# open-lux-B.net
KiCad netlist of a schematic drawn in EAGLE
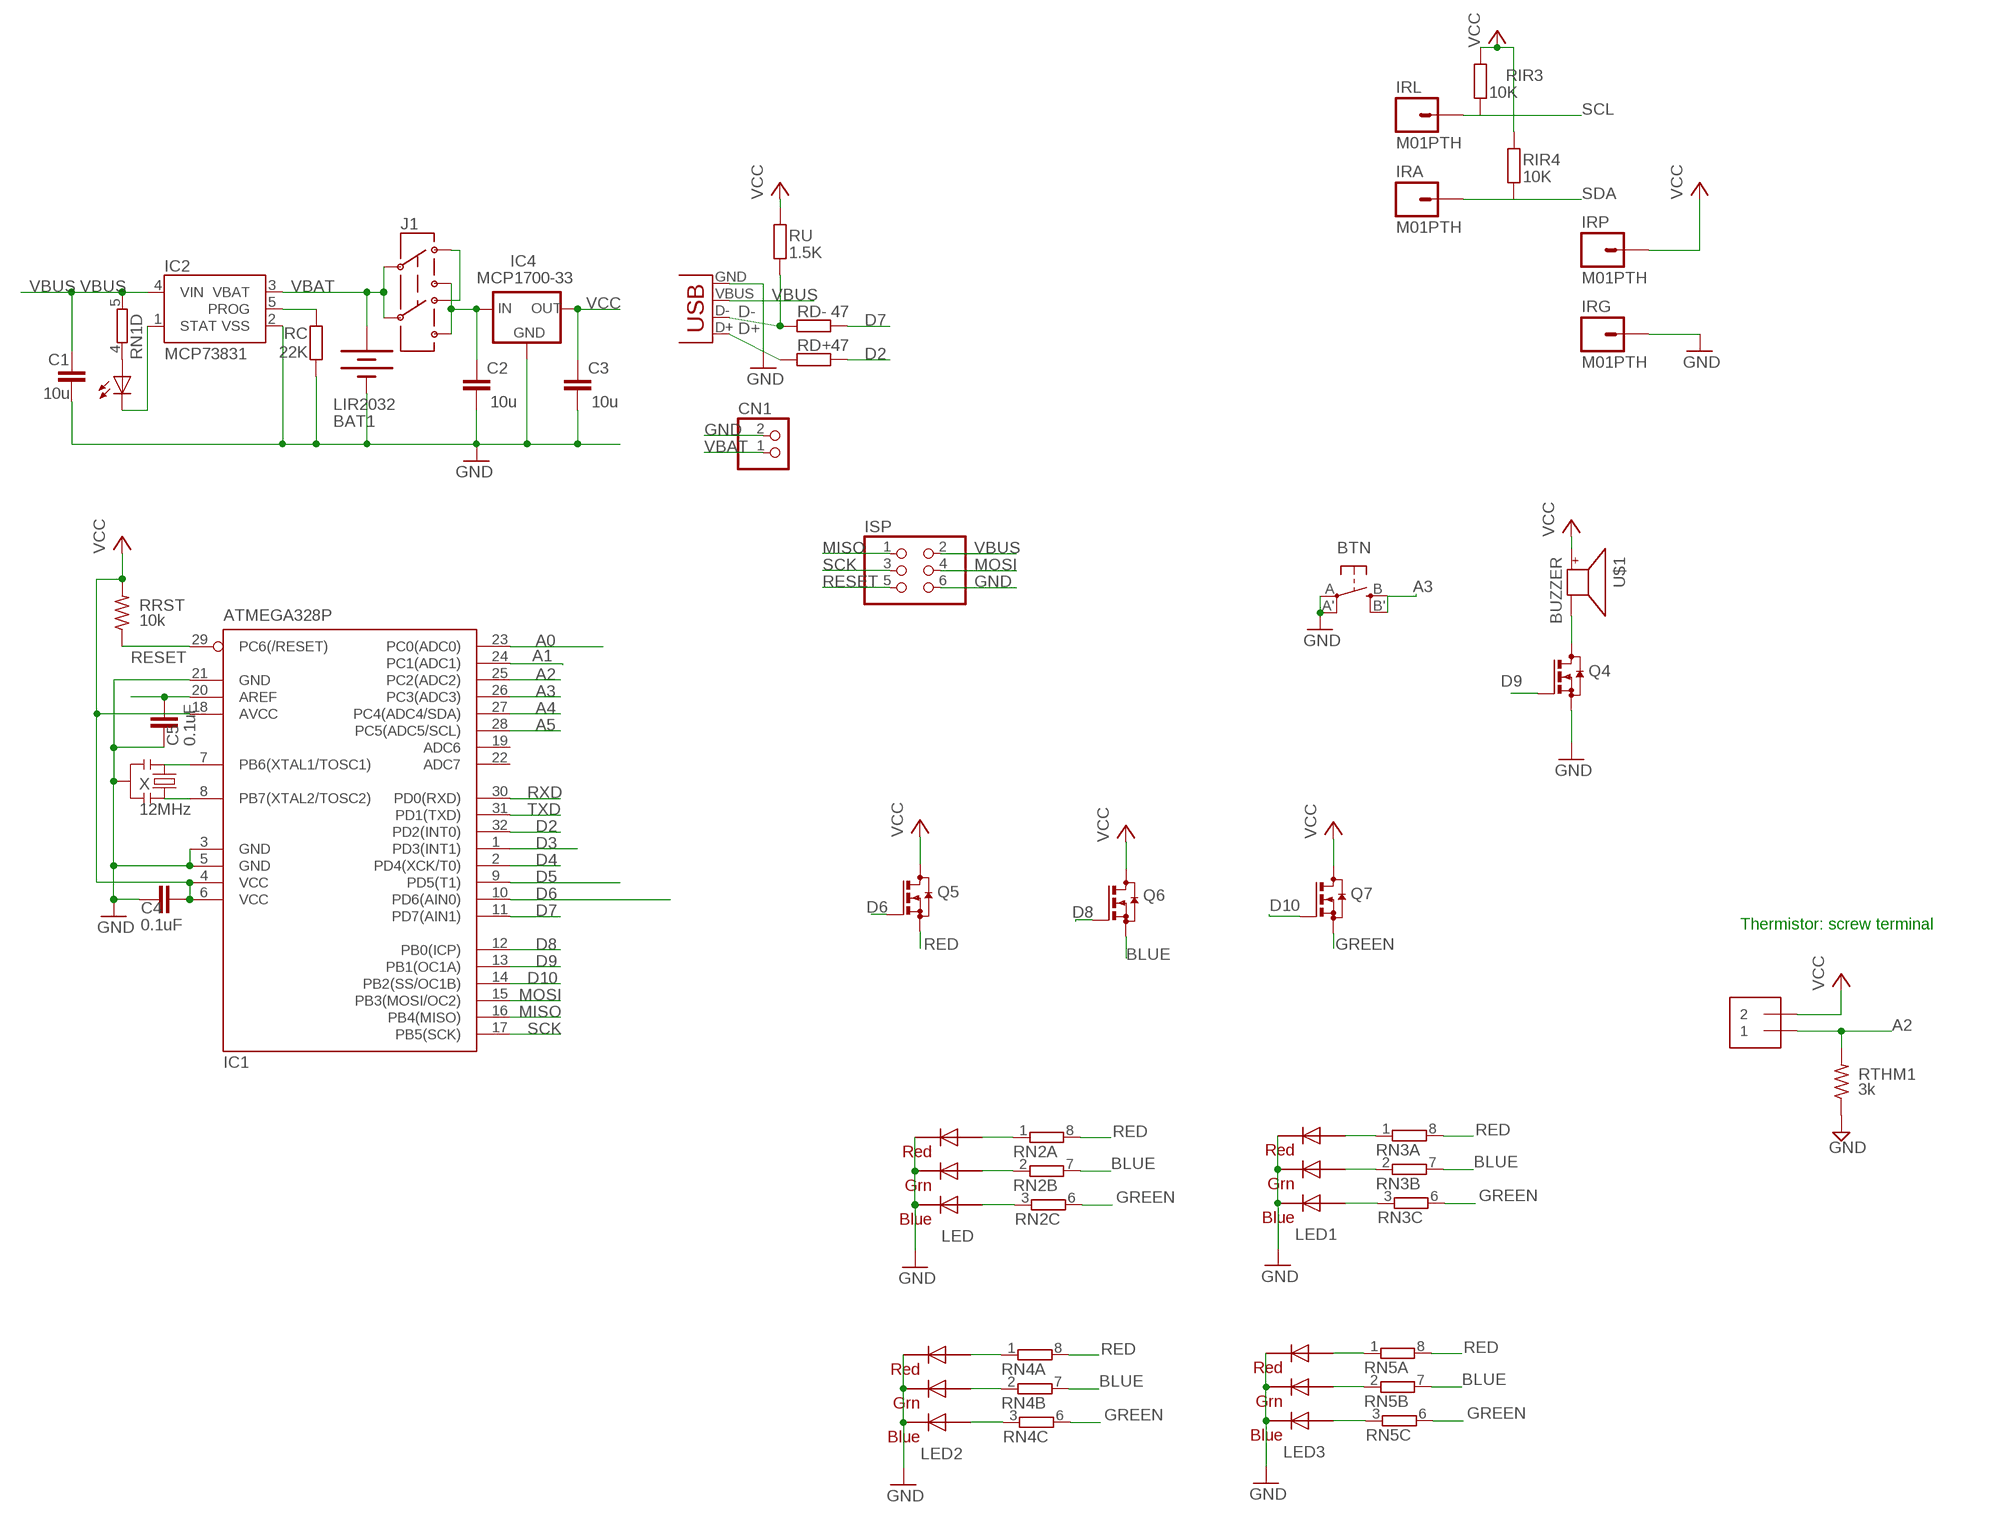
[diagram p0: schematic, sheet 1, part 1 of 2]
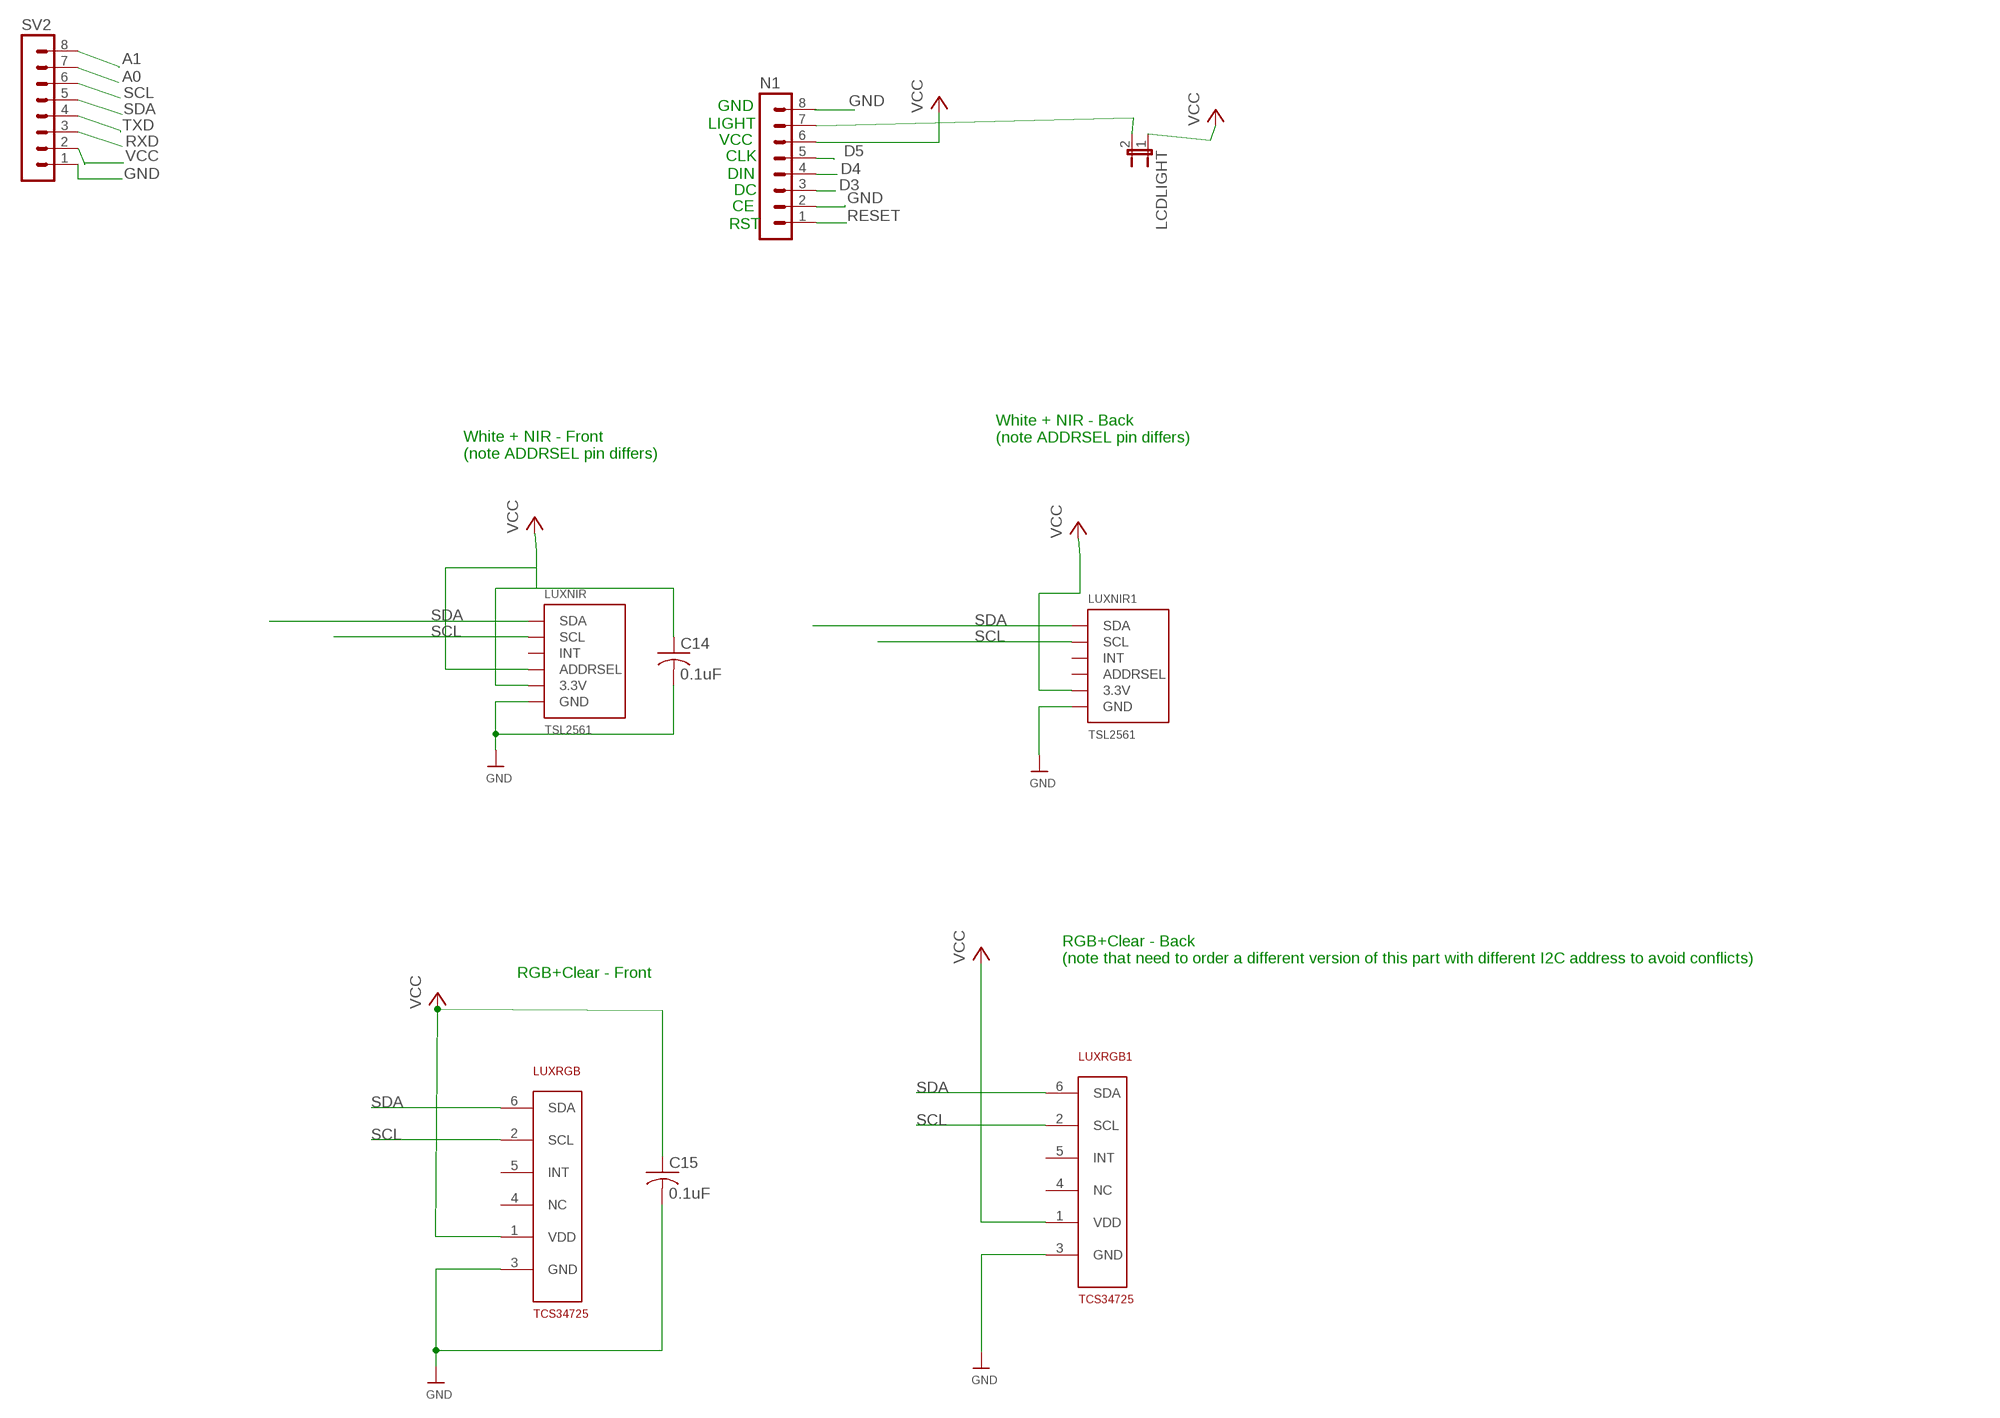
[diagram p1: schematic, sheet 1, part 2 of 2]

(export (version "E")
  (design (tool "Eeschema 10.0.6"))
  (components
    (comp (ref "BAT1")
      (value "LIR2032")
      (footprint "eagle-import:BATTCOM_20MM_PTH_SMT")
      (libsource (lib "eagle-import") (part "BATTERYBATTCOM_20MM_PTH_SMT"))
    )
    (comp (ref "BTN")
      (value "EVQQ2")
      (footprint "eagle-import:EVQ-Q2")
      (libsource (lib "eagle-import") (part "EVQQ2"))
    )
    (comp (ref "C1")
      (value "10u")
      (footprint "eagle-import:C0805")
      (libsource (lib "eagle-import") (part "resistor_C-EUC0805"))
    )
    (comp (ref "C2")
      (value "10u")
      (footprint "eagle-import:C0805")
      (libsource (lib "eagle-import") (part "resistor_C-EUC0805"))
    )
    (comp (ref "C3")
      (value "10u")
      (footprint "eagle-import:C0805")
      (libsource (lib "eagle-import") (part "resistor_C-EUC0805"))
    )
    (comp (ref "C4")
      (value "0.1uF")
      (footprint "eagle-import:C0805")
      (libsource (lib "eagle-import") (part "C-EUC0805"))
    )
    (comp (ref "C5")
      (value "0.1uF")
      (footprint "eagle-import:C0805")
      (libsource (lib "eagle-import") (part "C-EUC0805"))
    )
    (comp (ref "C14")
      (value "0.1uF")
      (footprint "eagle-import:C0805")
      (libsource (lib "eagle-import") (part "C-USC0805"))
    )
    (comp (ref "C15")
      (value "0.1uF")
      (footprint "eagle-import:C0805")
      (libsource (lib "eagle-import") (part "C-USC0805"))
    )
    (comp (ref "CHG")
      (value "0805")
      (footprint "eagle-import:CHIPLED_0805")
      (libsource (lib "eagle-import") (part "LEDCHIPLED_0805"))
    )
    (comp (ref "CN1")
      (value "JST_2PIN-SMT-RA")
      (footprint "eagle-import:JST-PH-2-SMT-RA")
      (libsource (lib "eagle-import") (part "JST_2PIN-SMT-RA"))
    )
    (comp (ref "IC1")
      (value "ATMEGA328P")
      (footprint "eagle-import:TQFP32-08")
      (fields (field (name "MPN") "ATMEGA8-16AU"))
      (libsource (lib "eagle-import") (part "MEGA8-AI"))
    )
    (comp (ref "IC2")
      (value "MCP73831")
      (footprint "eagle-import:SOT23-5")
      (libsource (lib "eagle-import") (part "MCP73831"))
    )
    (comp (ref "IC4")
      (value "MCP1700-33")
      (footprint "eagle-import:SOT23")
      (libsource (lib "eagle-import") (part "MCP1700SOT233"))
    )
    (comp (ref "IRA")
      (value "M01PTH")
      (footprint "eagle-import:1X01")
      (libsource (lib "eagle-import") (part "M01PTH"))
    )
    (comp (ref "IRG")
      (value "M01PTH")
      (footprint "eagle-import:1X01")
      (libsource (lib "eagle-import") (part "M01PTH"))
    )
    (comp (ref "IRL")
      (value "M01PTH")
      (footprint "eagle-import:1X01")
      (libsource (lib "eagle-import") (part "M01PTH"))
    )
    (comp (ref "IRP")
      (value "M01PTH")
      (footprint "eagle-import:1X01")
      (libsource (lib "eagle-import") (part "M01PTH"))
    )
    (comp (ref "ISP")
      (value "PINHD-2X3")
      (footprint "eagle-import:2X03")
      (libsource (lib "eagle-import") (part "PINHD-2X3"))
    )
    (comp (ref "J1")
      (value "AYZ0202")
      (footprint "eagle-import:AYZ0202")
      (libsource (lib "eagle-import") (part "AYZ0202"))
    )
    (comp (ref "LCDLIGHT")
      (value "JP1E")
      (footprint "eagle-import:JP1")
      (libsource (lib "eagle-import") (part "JP1E"))
    )
    (comp (ref "LED")
      (value "RGBLED5050")
      (footprint "eagle-import:RGBLED5050")
      (libsource (lib "eagle-import") (part "RGBLED5050"))
    )
    (comp (ref "LED1")
      (value "RGBLED5050")
      (footprint "eagle-import:RGBLED5050")
      (libsource (lib "eagle-import") (part "RGBLED5050"))
    )
    (comp (ref "LED2")
      (value "RGBLED5050")
      (footprint "eagle-import:RGBLED5050")
      (libsource (lib "eagle-import") (part "RGBLED5050"))
    )
    (comp (ref "LED3")
      (value "RGBLED5050")
      (footprint "eagle-import:RGBLED5050")
      (libsource (lib "eagle-import") (part "RGBLED5050"))
    )
    (comp (ref "LUXNIR")
      (value "TSL2561")
      (footprint "eagle-import:TSL2561_FN@1")
      (libsource (lib "eagle-import") (part "TSL2561"))
    )
    (comp (ref "LUXNIR1")
      (value "TSL2561")
      (footprint "eagle-import:TSL2561_FN@1")
      (libsource (lib "eagle-import") (part "TSL2561"))
    )
    (comp (ref "LUXRGB")
      (value "TCS34725")
      (footprint "eagle-import:DFN-6")
      (libsource (lib "eagle-import") (part "TCS34725"))
    )
    (comp (ref "LUXRGB1")
      (value "TCS34725")
      (footprint "eagle-import:DFN-6")
      (libsource (lib "eagle-import") (part "TCS34725"))
    )
    (comp (ref "N1")
      (value "MA08-1")
      (footprint "eagle-import:MA08-1")
      (libsource (lib "eagle-import") (part "MA08-1"))
    )
    (comp (ref "Q4")
      (value "BSS123")
      (footprint "eagle-import:SOT23")
      (libsource (lib "eagle-import") (part "BSS123"))
    )
    (comp (ref "Q5")
      (value "BSS123")
      (footprint "eagle-import:SOT23")
      (libsource (lib "eagle-import") (part "BSS123"))
    )
    (comp (ref "Q6")
      (value "BSS123")
      (footprint "eagle-import:SOT23")
      (libsource (lib "eagle-import") (part "BSS123"))
    )
    (comp (ref "Q7")
      (value "BSS123")
      (footprint "eagle-import:SOT23")
      (libsource (lib "eagle-import") (part "BSS123"))
    )
    (comp (ref "RC")
      (value "22K")
      (footprint "eagle-import:R0805")
      (libsource (lib "eagle-import") (part "R-EU_R0805"))
    )
    (comp (ref "RD+")
      (value "47")
      (footprint "eagle-import:R0805")
      (libsource (lib "eagle-import") (part "R-EU_R0805"))
    )
    (comp (ref "RD-")
      (value "47")
      (footprint "eagle-import:R0805")
      (libsource (lib "eagle-import") (part "R-EU_R0805"))
    )
    (comp (ref "RIR3")
      (value "10K")
      (footprint "eagle-import:R0805")
      (libsource (lib "eagle-import") (part "R-EU_R0805"))
    )
    (comp (ref "RIR4")
      (value "10K")
      (footprint "eagle-import:R0805")
      (libsource (lib "eagle-import") (part "R-EU_R0805"))
    )
    (comp (ref "RN1")
      (value "4R-NEXB38V")
      (footprint "eagle-import:EXB38V")
      (libsource (lib "eagle-import") (part "4R-NEXB38V"))
    )
    (comp (ref "RN2")
      (value "4R-NEXB38V")
      (footprint "eagle-import:EXB38V")
      (libsource (lib "eagle-import") (part "4R-NEXB38V"))
    )
    (comp (ref "RN3")
      (value "4R-NEXB38V")
      (footprint "eagle-import:EXB38V")
      (libsource (lib "eagle-import") (part "4R-NEXB38V"))
    )
    (comp (ref "RN4")
      (value "4R-NEXB38V")
      (footprint "eagle-import:EXB38V")
      (libsource (lib "eagle-import") (part "4R-NEXB38V"))
    )
    (comp (ref "RN5")
      (value "4R-NEXB38V")
      (footprint "eagle-import:EXB38V")
      (libsource (lib "eagle-import") (part "4R-NEXB38V"))
    )
    (comp (ref "RRST")
      (value "10k")
      (footprint "eagle-import:R0805@1")
      (libsource (lib "eagle-import") (part "R-US_R0805"))
    )
    (comp (ref "RTHM1")
      (value "3k")
      (footprint "eagle-import:R0805@1")
      (libsource (lib "eagle-import") (part "R-US_R0805"))
    )
    (comp (ref "RU")
      (value "1.5K")
      (footprint "eagle-import:R0805")
      (libsource (lib "eagle-import") (part "R-EU_R0805"))
    )
    (comp (ref "SV2")
      (value "MA08-1")
      (footprint "eagle-import:MA08-1")
      (libsource (lib "eagle-import") (part "MA08-1"))
    )
    (comp (ref "THM1")
      (value "1X2-3.5MM")
      (footprint "eagle-import:1X2-3.5MM")
      (libsource (lib "eagle-import") (part "1X2-3.5MM"))
    )
    (comp (ref "U$1")
      (value "BUZZER")
      (footprint "eagle-import:SMT-8585-BUZZER")
      (libsource (lib "eagle-import") (part "BUZZER"))
    )
    (comp (ref "X")
      (value "12MHz")
      (footprint "eagle-import:RESONATOR-SMD")
      (libsource (lib "eagle-import") (part "RESONATORSMD"))
    )
    (comp (ref "X1")
      (value "USBSMD")
      (footprint "eagle-import:USB-MINIB")
      (libsource (lib "eagle-import") (part "USBSMD"))
    )
  )
  (nets
    (net (code "1") (name "/A0") (class "Default")
      (node (ref "IC1") (pin "23") (pinfunction "PC0(ADC0)_23") (pintype "bidirectional"))
      (node (ref "SV2") (pin "7") (pinfunction "7_7") (pintype "passive"))
    )
    (net (code "2") (name "/A1") (class "Default")
      (node (ref "IC1") (pin "24") (pinfunction "PC1(ADC1)_24") (pintype "bidirectional"))
      (node (ref "SV2") (pin "8") (pinfunction "8_8") (pintype "passive"))
    )
    (net (code "3") (name "/A2") (class "Default")
      (node (ref "IC1") (pin "25") (pinfunction "PC2(ADC2)_25") (pintype "bidirectional"))
      (node (ref "RTHM1") (pin "2") (pinfunction "2_2") (pintype "passive"))
      (node (ref "THM1") (pin "1") (pinfunction "1_1") (pintype "passive"))
    )
    (net (code "4") (name "/A3") (class "Default")
      (node (ref "BTN") (pin "B") (pinfunction "S_B") (pintype "passive"))
      (node (ref "BTN") (pin "B'") (pinfunction "S1_B'") (pintype "passive"))
      (node (ref "IC1") (pin "26") (pinfunction "PC3(ADC3)_26") (pintype "bidirectional"))
    )
    (net (code "5") (name "/A4") (class "Default")
      (node (ref "IC1") (pin "27") (pinfunction "PC4(ADC4/SDA)_27") (pintype "bidirectional"))
    )
    (net (code "6") (name "/A5") (class "Default")
      (node (ref "IC1") (pin "28") (pinfunction "PC5(ADC5/SCL)_28") (pintype "bidirectional"))
    )
    (net (code "7") (name "/BLUE") (class "Default")
      (node (ref "Q6") (pin "2") (pinfunction "S_2") (pintype "passive"))
      (node (ref "RN2") (pin "7") (pinfunction "2_7") (pintype "passive"))
      (node (ref "RN3") (pin "7") (pinfunction "2_7") (pintype "passive"))
      (node (ref "RN4") (pin "7") (pinfunction "2_7") (pintype "passive"))
      (node (ref "RN5") (pin "7") (pinfunction "2_7") (pintype "passive"))
    )
    (net (code "8") (name "/D+") (class "Default")
      (node (ref "RD+") (pin "1") (pinfunction "1_1") (pintype "passive"))
      (node (ref "X1") (pin "D+") (pinfunction "D+_D+") (pintype "bidirectional"))
    )
    (net (code "9") (name "/D-") (class "Default")
      (node (ref "RD-") (pin "1") (pinfunction "1_1") (pintype "passive"))
      (node (ref "RU") (pin "1") (pinfunction "1_1") (pintype "passive"))
      (node (ref "X1") (pin "D-") (pinfunction "D-_D-") (pintype "bidirectional"))
    )
    (net (code "10") (name "/D2") (class "Default")
      (node (ref "IC1") (pin "32") (pinfunction "PD2(INT0)_32") (pintype "bidirectional"))
      (node (ref "RD+") (pin "2") (pinfunction "2_2") (pintype "passive"))
    )
    (net (code "11") (name "/D3") (class "Default")
      (node (ref "IC1") (pin "1") (pinfunction "PD3(INT1)_1") (pintype "bidirectional"))
      (node (ref "N1") (pin "3") (pinfunction "3_3") (pintype "passive"))
    )
    (net (code "12") (name "/D4") (class "Default")
      (node (ref "IC1") (pin "2") (pinfunction "PD4(XCK/T0)_2") (pintype "bidirectional"))
      (node (ref "N1") (pin "4") (pinfunction "4_4") (pintype "passive"))
    )
    (net (code "13") (name "/D5") (class "Default")
      (node (ref "IC1") (pin "9") (pinfunction "PD5(T1)_9") (pintype "bidirectional"))
      (node (ref "N1") (pin "5") (pinfunction "5_5") (pintype "passive"))
    )
    (net (code "14") (name "/D6") (class "Default")
      (node (ref "IC1") (pin "10") (pinfunction "PD6(AIN0)_10") (pintype "bidirectional"))
      (node (ref "Q5") (pin "1") (pinfunction "G_1") (pintype "passive"))
    )
    (net (code "15") (name "/D7") (class "Default")
      (node (ref "IC1") (pin "11") (pinfunction "PD7(AIN1)_11") (pintype "bidirectional"))
      (node (ref "RD-") (pin "2") (pinfunction "2_2") (pintype "passive"))
    )
    (net (code "16") (name "/D8") (class "Default")
      (node (ref "IC1") (pin "12") (pinfunction "PB0(ICP)_12") (pintype "bidirectional"))
      (node (ref "Q6") (pin "1") (pinfunction "G_1") (pintype "passive"))
    )
    (net (code "17") (name "/D9") (class "Default")
      (node (ref "IC1") (pin "13") (pinfunction "PB1(OC1A)_13") (pintype "bidirectional"))
      (node (ref "Q4") (pin "1") (pinfunction "G_1") (pintype "passive"))
    )
    (net (code "18") (name "/D10") (class "Default")
      (node (ref "IC1") (pin "14") (pinfunction "PB2(SS/OC1B)_14") (pintype "bidirectional"))
      (node (ref "Q7") (pin "1") (pinfunction "G_1") (pintype "passive"))
    )
    (net (code "19") (name "/GREEN") (class "Default")
      (node (ref "Q7") (pin "2") (pinfunction "S_2") (pintype "passive"))
      (node (ref "RN2") (pin "6") (pinfunction "2_6") (pintype "passive"))
      (node (ref "RN3") (pin "6") (pinfunction "2_6") (pintype "passive"))
      (node (ref "RN4") (pin "6") (pinfunction "2_6") (pintype "passive"))
      (node (ref "RN5") (pin "6") (pinfunction "2_6") (pintype "passive"))
    )
    (net (code "20") (name "/MISO") (class "Default")
      (node (ref "IC1") (pin "16") (pinfunction "PB4(MISO)_16") (pintype "bidirectional"))
      (node (ref "ISP") (pin "1") (pinfunction "1_1") (pintype "passive"))
    )
    (net (code "21") (name "/MOSI") (class "Default")
      (node (ref "IC1") (pin "15") (pinfunction "PB3(MOSI/OC2)_15") (pintype "bidirectional"))
      (node (ref "ISP") (pin "4") (pinfunction "4_4") (pintype "passive"))
    )
    (net (code "22") (name "/RED") (class "Default")
      (node (ref "Q5") (pin "2") (pinfunction "S_2") (pintype "passive"))
      (node (ref "RN2") (pin "8") (pinfunction "2_8") (pintype "passive"))
      (node (ref "RN3") (pin "8") (pinfunction "2_8") (pintype "passive"))
      (node (ref "RN4") (pin "8") (pinfunction "2_8") (pintype "passive"))
      (node (ref "RN5") (pin "8") (pinfunction "2_8") (pintype "passive"))
    )
    (net (code "23") (name "/RESET") (class "Default")
      (node (ref "IC1") (pin "29") (pinfunction "PC6(/RESET)_29") (pintype "bidirectional"))
      (node (ref "ISP") (pin "5") (pinfunction "5_5") (pintype "passive"))
      (node (ref "N1") (pin "1") (pinfunction "1_1") (pintype "passive"))
      (node (ref "RRST") (pin "1") (pinfunction "1_1") (pintype "passive"))
    )
    (net (code "24") (name "/RXD") (class "Default")
      (node (ref "IC1") (pin "30") (pinfunction "PD0(RXD)_30") (pintype "bidirectional"))
      (node (ref "SV2") (pin "3") (pinfunction "3_3") (pintype "passive"))
    )
    (net (code "25") (name "/SCK") (class "Default")
      (node (ref "IC1") (pin "17") (pinfunction "PB5(SCK)_17") (pintype "bidirectional"))
      (node (ref "ISP") (pin "3") (pinfunction "3_3") (pintype "passive"))
    )
    (net (code "26") (name "/SCL") (class "Default")
      (node (ref "IRL") (pin "1") (pinfunction "1_1") (pintype "passive"))
      (node (ref "LUXNIR") (pin "CLK") (pinfunction "SCL_CLK") (pintype "bidirectional"))
      (node (ref "LUXNIR1") (pin "CLK") (pinfunction "SCL_CLK") (pintype "bidirectional"))
      (node (ref "LUXRGB") (pin "2") (pinfunction "SCL_2") (pintype "bidirectional"))
      (node (ref "LUXRGB1") (pin "2") (pinfunction "SCL_2") (pintype "bidirectional"))
      (node (ref "RIR3") (pin "1") (pinfunction "1_1") (pintype "passive"))
      (node (ref "SV2") (pin "6") (pinfunction "6_6") (pintype "passive"))
    )
    (net (code "27") (name "/SDA") (class "Default")
      (node (ref "IRA") (pin "1") (pinfunction "1_1") (pintype "passive"))
      (node (ref "LUXNIR") (pin "DATA") (pinfunction "SDA_DATA") (pintype "bidirectional"))
      (node (ref "LUXNIR1") (pin "DATA") (pinfunction "SDA_DATA") (pintype "bidirectional"))
      (node (ref "LUXRGB") (pin "6") (pinfunction "SDA_6") (pintype "bidirectional"))
      (node (ref "LUXRGB1") (pin "6") (pinfunction "SDA_6") (pintype "bidirectional"))
      (node (ref "RIR4") (pin "1") (pinfunction "1_1") (pintype "passive"))
      (node (ref "SV2") (pin "5") (pinfunction "5_5") (pintype "passive"))
    )
    (net (code "28") (name "/TXD") (class "Default")
      (node (ref "IC1") (pin "31") (pinfunction "PD1(TXD)_31") (pintype "bidirectional"))
      (node (ref "SV2") (pin "4") (pinfunction "4_4") (pintype "passive"))
    )
    (net (code "29") (name "/VBAT") (class "Default")
      (node (ref "BAT1") (pin "P$2") (pinfunction "+_P$2") (pintype "power_in"))
      (node (ref "CN1") (pin "1") (pinfunction "2_1") (pintype "passive"))
      (node (ref "IC2") (pin "3") (pinfunction "VBAT_3") (pintype "power_in"))
      (node (ref "J1") (pin "2") (pinfunction "2_2") (pintype "bidirectional"))
      (node (ref "J1") (pin "5") (pinfunction "5_5") (pintype "bidirectional"))
    )
    (net (code "30") (name "/VBUS") (class "Default")
      (node (ref "C1") (pin "1") (pinfunction "1_1") (pintype "passive"))
      (node (ref "IC2") (pin "4") (pinfunction "VIN_4") (pintype "power_in"))
      (node (ref "ISP") (pin "2") (pinfunction "2_2") (pintype "passive"))
      (node (ref "RN1") (pin "5") (pinfunction "2_5") (pintype "passive"))
      (node (ref "X1") (pin "VBUS") (pinfunction "VBUS_VBUS") (pintype "bidirectional"))
    )
    (net (code "31") (name "GND") (class "Default")
      (node (ref "BAT1") (pin "P$1") (pinfunction "-_P$1") (pintype "power_in"))
      (node (ref "BTN") (pin "A") (pinfunction "P_A") (pintype "passive"))
      (node (ref "BTN") (pin "A'") (pinfunction "P1_A'") (pintype "passive"))
      (node (ref "C1") (pin "2") (pinfunction "2_2") (pintype "passive"))
      (node (ref "C14") (pin "2") (pinfunction "2_2") (pintype "passive"))
      (node (ref "C15") (pin "2") (pinfunction "2_2") (pintype "passive"))
      (node (ref "C2") (pin "2") (pinfunction "2_2") (pintype "passive"))
      (node (ref "C3") (pin "2") (pinfunction "2_2") (pintype "passive"))
      (node (ref "C4") (pin "1") (pinfunction "1_1") (pintype "passive"))
      (node (ref "C5") (pin "1") (pinfunction "1_1") (pintype "passive"))
      (node (ref "CN1") (pin "2") (pinfunction "1_2") (pintype "passive"))
      (node (ref "IC1") (pin "21") (pinfunction "GND_21") (pintype "power_in"))
      (node (ref "IC1") (pin "3") (pinfunction "GND_3") (pintype "power_in"))
      (node (ref "IC1") (pin "5") (pinfunction "GND_5") (pintype "power_in"))
      (node (ref "IC2") (pin "2") (pinfunction "VSS_2") (pintype "power_in"))
      (node (ref "IC4") (pin "1") (pinfunction "GND_1") (pintype "input"))
      (node (ref "IRG") (pin "1") (pinfunction "1_1") (pintype "passive"))
      (node (ref "ISP") (pin "6") (pinfunction "6_6") (pintype "passive"))
      (node (ref "LED") (pin "4") (pinfunction "BLUE_C_4") (pintype "bidirectional"))
      (node (ref "LED") (pin "5") (pinfunction "RED_C_5") (pintype "bidirectional"))
      (node (ref "LED") (pin "6") (pinfunction "GREEN_C_6") (pintype "bidirectional"))
      (node (ref "LED1") (pin "4") (pinfunction "BLUE_C_4") (pintype "bidirectional"))
      (node (ref "LED1") (pin "5") (pinfunction "RED_C_5") (pintype "bidirectional"))
      (node (ref "LED1") (pin "6") (pinfunction "GREEN_C_6") (pintype "bidirectional"))
      (node (ref "LED2") (pin "4") (pinfunction "BLUE_C_4") (pintype "bidirectional"))
      (node (ref "LED2") (pin "5") (pinfunction "RED_C_5") (pintype "bidirectional"))
      (node (ref "LED2") (pin "6") (pinfunction "GREEN_C_6") (pintype "bidirectional"))
      (node (ref "LED3") (pin "4") (pinfunction "BLUE_C_4") (pintype "bidirectional"))
      (node (ref "LED3") (pin "5") (pinfunction "RED_C_5") (pintype "bidirectional"))
      (node (ref "LED3") (pin "6") (pinfunction "GREEN_C_6") (pintype "bidirectional"))
      (node (ref "LUXNIR") (pin "VSS") (pinfunction "GND_VSS") (pintype "bidirectional"))
      (node (ref "LUXNIR1") (pin "VSS") (pinfunction "GND_VSS") (pintype "bidirectional"))
      (node (ref "LUXRGB") (pin "3") (pinfunction "GND_3") (pintype "bidirectional"))
      (node (ref "LUXRGB1") (pin "3") (pinfunction "GND_3") (pintype "bidirectional"))
      (node (ref "N1") (pin "2") (pinfunction "2_2") (pintype "passive"))
      (node (ref "N1") (pin "8") (pinfunction "8_8") (pintype "passive"))
      (node (ref "Q4") (pin "2") (pinfunction "S_2") (pintype "passive"))
      (node (ref "RC") (pin "1") (pinfunction "1_1") (pintype "passive"))
      (node (ref "RTHM1") (pin "1") (pinfunction "1_1") (pintype "passive"))
      (node (ref "SV2") (pin "1") (pinfunction "1_1") (pintype "passive"))
      (node (ref "X") (pin "2") (pinfunction "2_2") (pintype "passive"))
      (node (ref "X1") (pin "GND") (pinfunction "GND_GND") (pintype "bidirectional"))
    )
    (net (code "32") (name "Net-(IC1-AREF)") (class "Default")
      (node (ref "C5") (pin "2") (pinfunction "2_2") (pintype "passive"))
      (node (ref "IC1") (pin "20") (pinfunction "AREF_20") (pintype "passive"))
    )
    (net (code "33") (name "Net-(IC1-PB6(XTAL1{slash}TOSC1))") (class "Default")
      (node (ref "IC1") (pin "7") (pinfunction "PB6(XTAL1/TOSC1)_7") (pintype "bidirectional"))
      (node (ref "X") (pin "1") (pinfunction "1_1") (pintype "passive"))
    )
    (net (code "34") (name "Net-(IC1-PB7(XTAL2{slash}TOSC2))") (class "Default")
      (node (ref "IC1") (pin "8") (pinfunction "PB7(XTAL2/TOSC2)_8") (pintype "bidirectional"))
      (node (ref "X") (pin "3") (pinfunction "3_3") (pintype "passive"))
    )
    (net (code "35") (name "Net-(IC2-PROG)") (class "Default")
      (node (ref "IC2") (pin "5") (pinfunction "PROG_5") (pintype "input"))
      (node (ref "RC") (pin "2") (pinfunction "2_2") (pintype "passive"))
    )
    (net (code "36") (name "Net-(IC2-STAT)") (class "Default")
      (node (ref "CHG") (pin "C") (pinfunction "C_C") (pintype "passive"))
      (node (ref "IC2") (pin "1") (pinfunction "STAT_1") (pintype "output"))
    )
    (net (code "37") (name "Net-(IC4-IN)") (class "Default")
      (node (ref "C2") (pin "1") (pinfunction "1_1") (pintype "passive"))
      (node (ref "IC4") (pin "3") (pinfunction "IN_3") (pintype "input"))
      (node (ref "J1") (pin "1") (pinfunction "3_1") (pintype "bidirectional"))
      (node (ref "J1") (pin "4") (pinfunction "6_4") (pintype "bidirectional"))
    )
    (net (code "38") (name "Net-(J1-1)") (class "Default")
      (node (ref "J1") (pin "3") (pinfunction "1_3") (pintype "bidirectional"))
      (node (ref "J1") (pin "6") (pinfunction "4_6") (pintype "bidirectional"))
    )
    (net (code "39") (name "Net-(LCDLIGHT-Pad2)") (class "Default")
      (node (ref "LCDLIGHT") (pin "2") (pinfunction "2_2") (pintype "passive"))
      (node (ref "N1") (pin "7") (pinfunction "7_7") (pintype "passive"))
    )
    (net (code "40") (name "Net-(LED-BLUE_A)") (class "Default")
      (node (ref "LED") (pin "3") (pinfunction "BLUE_A_3") (pintype "bidirectional"))
      (node (ref "RN2") (pin "3") (pinfunction "1_3") (pintype "passive"))
    )
    (net (code "41") (name "Net-(LED-GREEN_A)") (class "Default")
      (node (ref "LED") (pin "1") (pinfunction "GREEN_A_1") (pintype "bidirectional"))
      (node (ref "RN2") (pin "2") (pinfunction "1_2") (pintype "passive"))
    )
    (net (code "42") (name "Net-(LED-RED_A)") (class "Default")
      (node (ref "LED") (pin "2") (pinfunction "RED_A_2") (pintype "bidirectional"))
      (node (ref "RN2") (pin "1") (pinfunction "1_1") (pintype "passive"))
    )
    (net (code "43") (name "Net-(LED1-BLUE_A)") (class "Default")
      (node (ref "LED1") (pin "3") (pinfunction "BLUE_A_3") (pintype "bidirectional"))
      (node (ref "RN3") (pin "3") (pinfunction "1_3") (pintype "passive"))
    )
    (net (code "44") (name "Net-(LED1-GREEN_A)") (class "Default")
      (node (ref "LED1") (pin "1") (pinfunction "GREEN_A_1") (pintype "bidirectional"))
      (node (ref "RN3") (pin "2") (pinfunction "1_2") (pintype "passive"))
    )
    (net (code "45") (name "Net-(LED1-RED_A)") (class "Default")
      (node (ref "LED1") (pin "2") (pinfunction "RED_A_2") (pintype "bidirectional"))
      (node (ref "RN3") (pin "1") (pinfunction "1_1") (pintype "passive"))
    )
    (net (code "46") (name "Net-(LED2-BLUE_A)") (class "Default")
      (node (ref "LED2") (pin "3") (pinfunction "BLUE_A_3") (pintype "bidirectional"))
      (node (ref "RN4") (pin "3") (pinfunction "1_3") (pintype "passive"))
    )
    (net (code "47") (name "Net-(LED2-GREEN_A)") (class "Default")
      (node (ref "LED2") (pin "1") (pinfunction "GREEN_A_1") (pintype "bidirectional"))
      (node (ref "RN4") (pin "2") (pinfunction "1_2") (pintype "passive"))
    )
    (net (code "48") (name "Net-(LED2-RED_A)") (class "Default")
      (node (ref "LED2") (pin "2") (pinfunction "RED_A_2") (pintype "bidirectional"))
      (node (ref "RN4") (pin "1") (pinfunction "1_1") (pintype "passive"))
    )
    (net (code "49") (name "Net-(LED3-BLUE_A)") (class "Default")
      (node (ref "LED3") (pin "3") (pinfunction "BLUE_A_3") (pintype "bidirectional"))
      (node (ref "RN5") (pin "3") (pinfunction "1_3") (pintype "passive"))
    )
    (net (code "50") (name "Net-(LED3-GREEN_A)") (class "Default")
      (node (ref "LED3") (pin "1") (pinfunction "GREEN_A_1") (pintype "bidirectional"))
      (node (ref "RN5") (pin "2") (pinfunction "1_2") (pintype "passive"))
    )
    (net (code "51") (name "Net-(LED3-RED_A)") (class "Default")
      (node (ref "LED3") (pin "2") (pinfunction "RED_A_2") (pintype "bidirectional"))
      (node (ref "RN5") (pin "1") (pinfunction "1_1") (pintype "passive"))
    )
    (net (code "52") (name "Net-(Q4-D)") (class "Default")
      (node (ref "Q4") (pin "3") (pinfunction "D_3") (pintype "passive"))
      (node (ref "U$1") (pin "-") (pinfunction "-_-") (pintype "passive"))
    )
    (net (code "53") (name "Net-(RN1D-1)") (class "Default")
      (node (ref "CHG") (pin "A") (pinfunction "A_A") (pintype "passive"))
      (node (ref "RN1") (pin "4") (pinfunction "1_4") (pintype "passive"))
    )
    (net (code "54") (name "VCC") (class "Default")
      (node (ref "C14") (pin "1") (pinfunction "1_1") (pintype "passive"))
      (node (ref "C15") (pin "1") (pinfunction "1_1") (pintype "passive"))
      (node (ref "C3") (pin "1") (pinfunction "1_1") (pintype "passive"))
      (node (ref "C4") (pin "2") (pinfunction "2_2") (pintype "passive"))
      (node (ref "IC1") (pin "18") (pinfunction "AVCC_18") (pintype "power_in"))
      (node (ref "IC1") (pin "4") (pinfunction "VCC_4") (pintype "power_in"))
      (node (ref "IC1") (pin "6") (pinfunction "VCC_6") (pintype "power_in"))
      (node (ref "IC4") (pin "2") (pinfunction "OUT_2") (pintype "passive"))
      (node (ref "IRP") (pin "1") (pinfunction "1_1") (pintype "passive"))
      (node (ref "LCDLIGHT") (pin "1") (pinfunction "1_1") (pintype "passive"))
      (node (ref "LUXNIR") (pin "ADR") (pinfunction "ADDRSEL_ADR") (pintype "bidirectional"))
      (node (ref "LUXNIR") (pin "VDD") (pinfunction "3.3V_VDD") (pintype "bidirectional"))
      (node (ref "LUXNIR1") (pin "VDD") (pinfunction "3.3V_VDD") (pintype "bidirectional"))
      (node (ref "LUXRGB") (pin "1") (pinfunction "VDD_1") (pintype "bidirectional"))
      (node (ref "LUXRGB1") (pin "1") (pinfunction "VDD_1") (pintype "bidirectional"))
      (node (ref "N1") (pin "6") (pinfunction "6_6") (pintype "passive"))
      (node (ref "Q5") (pin "3") (pinfunction "D_3") (pintype "passive"))
      (node (ref "Q6") (pin "3") (pinfunction "D_3") (pintype "passive"))
      (node (ref "Q7") (pin "3") (pinfunction "D_3") (pintype "passive"))
      (node (ref "RIR3") (pin "2") (pinfunction "2_2") (pintype "passive"))
      (node (ref "RIR4") (pin "2") (pinfunction "2_2") (pintype "passive"))
      (node (ref "RRST") (pin "2") (pinfunction "2_2") (pintype "passive"))
      (node (ref "RU") (pin "2") (pinfunction "2_2") (pintype "passive"))
      (node (ref "SV2") (pin "2") (pinfunction "2_2") (pintype "passive"))
      (node (ref "THM1") (pin "2") (pinfunction "2_2") (pintype "passive"))
      (node (ref "U$1") (pin "+") (pinfunction "+_+") (pintype "passive"))
    )
    (net (code "55") (name "unconnected-(IC1-ADC6-Pad19)") (class "Default")
      (node (ref "IC1") (pin "19") (pinfunction "ADC6_19") (pintype "bidirectional"))
    )
    (net (code "56") (name "unconnected-(IC1-ADC7-Pad22)") (class "Default")
      (node (ref "IC1") (pin "22") (pinfunction "ADC7_22") (pintype "bidirectional"))
    )
    (net (code "57") (name "unconnected-(LUXNIR-PadINT)") (class "Default")
      (node (ref "LUXNIR") (pin "INT") (pinfunction "INT_INT") (pintype "bidirectional"))
    )
    (net (code "58") (name "unconnected-(LUXNIR1-ADDRSEL-PadADR)") (class "Default")
      (node (ref "LUXNIR1") (pin "ADR") (pinfunction "ADDRSEL_ADR") (pintype "bidirectional"))
    )
    (net (code "59") (name "unconnected-(LUXNIR1-PadINT)") (class "Default")
      (node (ref "LUXNIR1") (pin "INT") (pinfunction "INT_INT") (pintype "bidirectional"))
    )
    (net (code "60") (name "unconnected-(LUXRGB-INT-Pad5)") (class "Default")
      (node (ref "LUXRGB") (pin "5") (pinfunction "INT_5") (pintype "bidirectional"))
    )
    (net (code "61") (name "unconnected-(LUXRGB-NC-Pad4)") (class "Default")
      (node (ref "LUXRGB") (pin "4") (pinfunction "NC_4") (pintype "bidirectional"))
    )
    (net (code "62") (name "unconnected-(LUXRGB1-INT-Pad5)") (class "Default")
      (node (ref "LUXRGB1") (pin "5") (pinfunction "INT_5") (pintype "bidirectional"))
    )
    (net (code "63") (name "unconnected-(LUXRGB1-NC-Pad4)") (class "Default")
      (node (ref "LUXRGB1") (pin "4") (pinfunction "NC_4") (pintype "bidirectional"))
    )
  )
)
